# solar.net
KiCad netlist of a schematic drawn in EAGLE
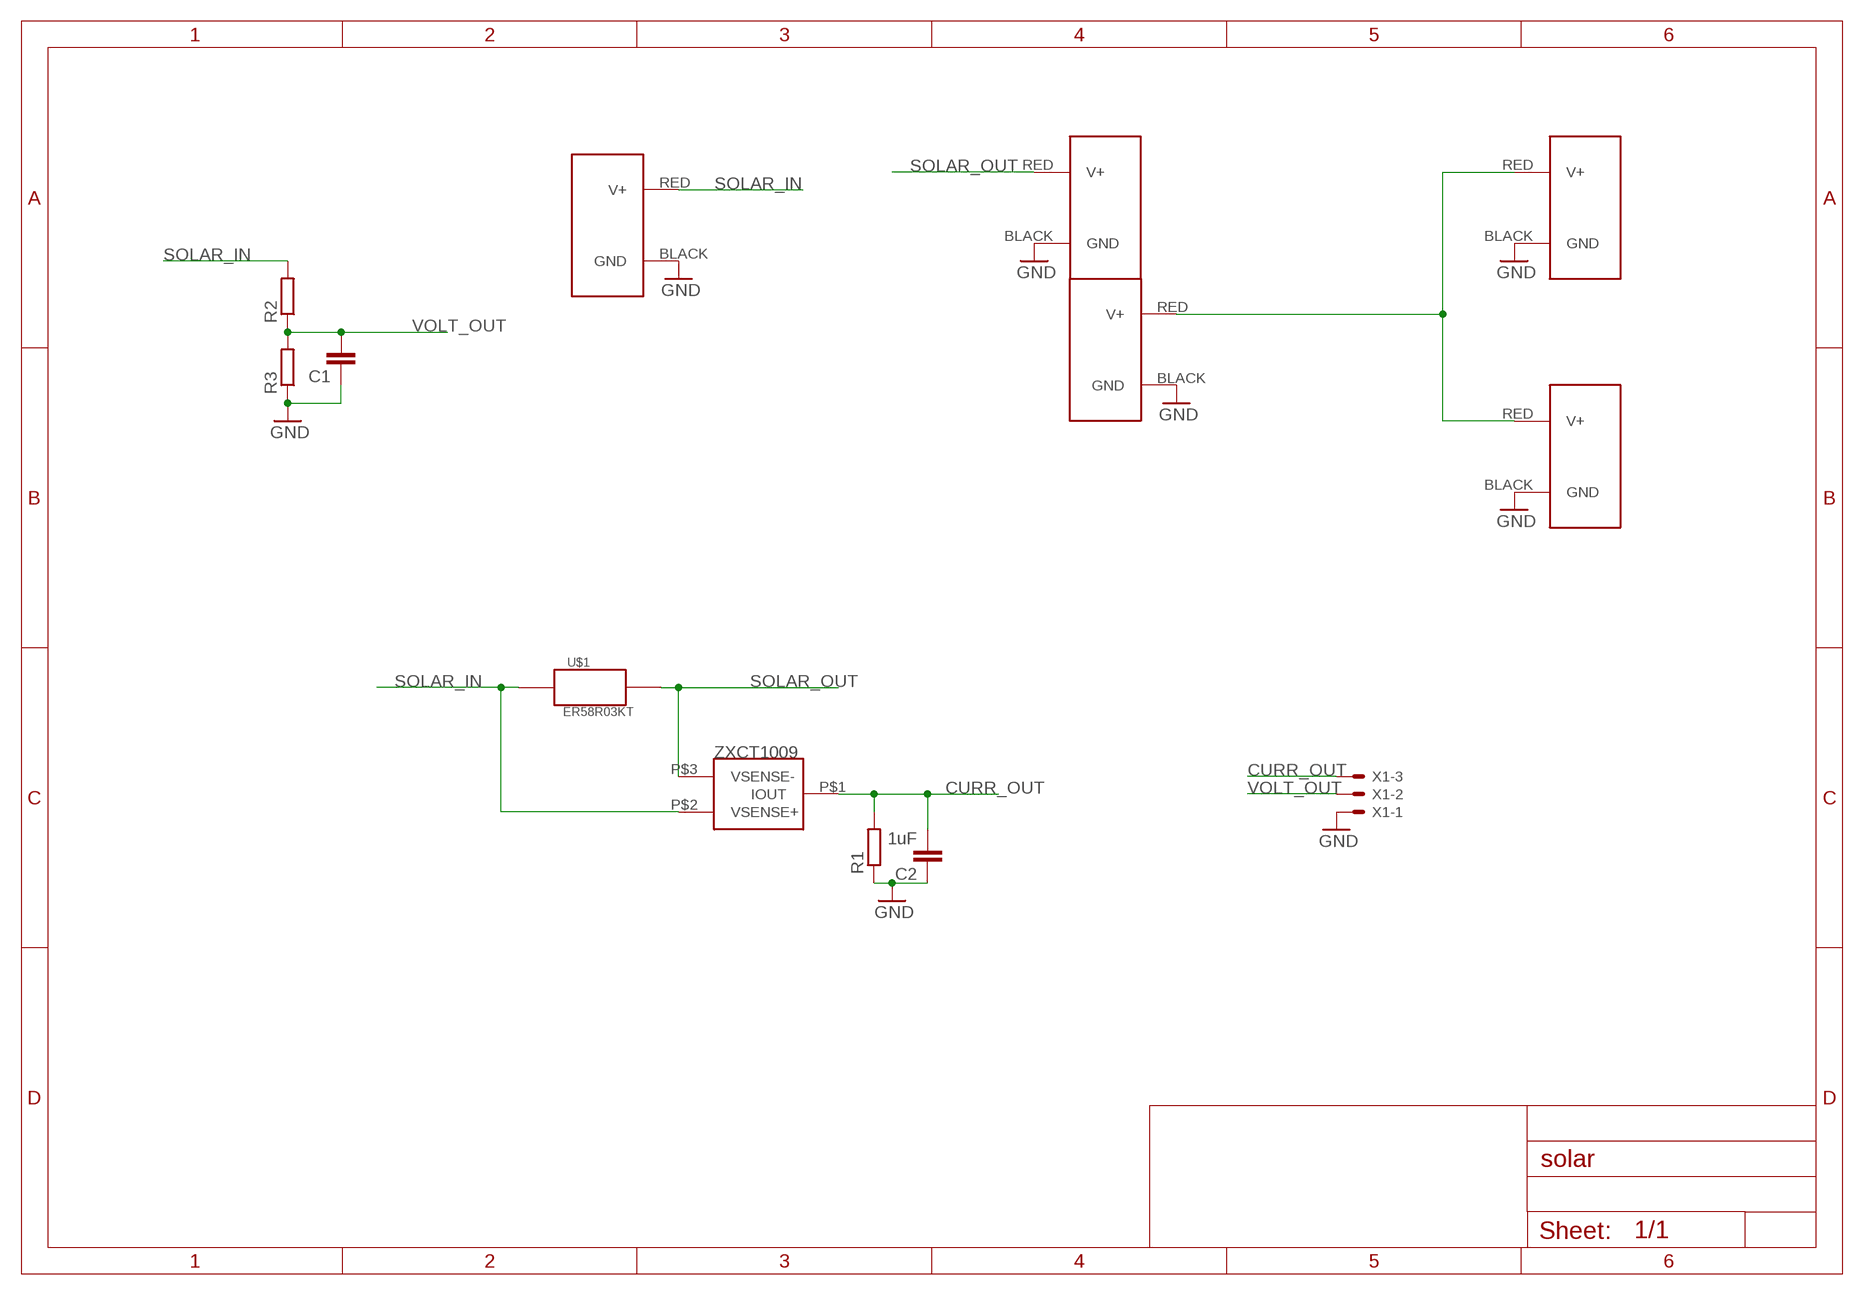
[diagram p0: schematic, sheet 1]

(export (version "E")
  (design (tool "Eeschema 10.0.6"))
  (components
    (comp (ref "C1")
      (value "C-EUC0805")
      (footprint "eagle-import:C0805")
      (libsource (lib "eagle-import") (part "C-EUC0805"))
    )
    (comp (ref "C2")
      (value "1uF")
      (footprint "eagle-import:C0805")
      (libsource (lib "eagle-import") (part "C-EUC0805"))
    )
    (comp (ref "J1")
      (value "POWERPOLE_POWER25A")
      (footprint "eagle-import:POWERPOLE_PAIR_25A")
      (libsource (lib "eagle-import") (part "POWERPOLE_POWER25A"))
    )
    (comp (ref "J2")
      (value "POWERPOLE_POWER25A")
      (footprint "eagle-import:POWERPOLE_PAIR_25A")
      (libsource (lib "eagle-import") (part "POWERPOLE_POWER25A"))
    )
    (comp (ref "J3")
      (value "POWERPOLE_POWER25A")
      (footprint "eagle-import:POWERPOLE_PAIR_25A")
      (libsource (lib "eagle-import") (part "POWERPOLE_POWER25A"))
    )
    (comp (ref "J4")
      (value "POWERPOLE_POWER25A")
      (footprint "eagle-import:POWERPOLE_PAIR_25A")
      (libsource (lib "eagle-import") (part "POWERPOLE_POWER25A"))
    )
    (comp (ref "J5")
      (value "POWERPOLE_POWER25A")
      (footprint "eagle-import:POWERPOLE_PAIR_25A")
      (libsource (lib "eagle-import") (part "POWERPOLE_POWER25A"))
    )
    (comp (ref "R1")
      (value "R-EU_R0805")
      (footprint "eagle-import:R0805")
      (libsource (lib "eagle-import") (part "R-EU_R0805"))
    )
    (comp (ref "R2")
      (value "R-EU_R0805")
      (footprint "eagle-import:R0805")
      (libsource (lib "eagle-import") (part "R-EU_R0805"))
    )
    (comp (ref "R3")
      (value "R-EU_R0805")
      (footprint "eagle-import:R0805")
      (libsource (lib "eagle-import") (part "R-EU_R0805"))
    )
    (comp (ref "U$1")
      (value "ER58R03KT")
      (footprint "eagle-import:ER58R03KT")
      (libsource (lib "eagle-import") (part "ER58R03KT"))
    )
    (comp (ref "U$2")
      (value "ZXCT1009")
      (footprint "eagle-import:ZXCT1009-SOT")
      (libsource (lib "eagle-import") (part "ZXCT1009"))
    )
    (comp (ref "X1")
      (value "KK-156-3")
      (footprint "eagle-import:KK-156-3")
      (libsource (lib "eagle-import") (part "KK-156-3"))
    )
  )
  (nets
    (net (code "1") (name "/CURR_OUT") (class "Default")
      (node (ref "C2") (pin "2") (pinfunction "2_2") (pintype "passive"))
      (node (ref "R1") (pin "2") (pinfunction "2_2") (pintype "passive"))
      (node (ref "U$2") (pin "P$1") (pinfunction "IOUT_P$1") (pintype "output"))
      (node (ref "X1") (pin "3") (pinfunction "S_3") (pintype "passive"))
    )
    (net (code "2") (name "/SOLAR_IN") (class "Default")
      (node (ref "J1") (pin "RED") (pinfunction "V+_RED") (pintype "power_in"))
      (node (ref "R2") (pin "2") (pinfunction "2_2") (pintype "passive"))
      (node (ref "U$1") (pin "P$1") (pinfunction "P$1_P$1") (pintype "passive"))
      (node (ref "U$2") (pin "P$2") (pinfunction "VSENSE+_P$2") (pintype "bidirectional"))
    )
    (net (code "3") (name "/SOLAR_OUT") (class "Default")
      (node (ref "J3") (pin "RED") (pinfunction "V+_RED") (pintype "power_in"))
      (node (ref "U$1") (pin "P$2") (pinfunction "P$2_P$2") (pintype "passive"))
      (node (ref "U$2") (pin "P$3") (pinfunction "VSENSE-_P$3") (pintype "input"))
    )
    (net (code "4") (name "/VOLT_OUT") (class "Default")
      (node (ref "C1") (pin "2") (pinfunction "2_2") (pintype "passive"))
      (node (ref "R2") (pin "1") (pinfunction "1_1") (pintype "passive"))
      (node (ref "R3") (pin "2") (pinfunction "2_2") (pintype "passive"))
      (node (ref "X1") (pin "2") (pinfunction "S_2") (pintype "passive"))
    )
    (net (code "5") (name "GND") (class "Default")
      (node (ref "C1") (pin "1") (pinfunction "1_1") (pintype "passive"))
      (node (ref "C2") (pin "1") (pinfunction "1_1") (pintype "passive"))
      (node (ref "J1") (pin "BLACK") (pinfunction "GND_BLACK") (pintype "power_in"))
      (node (ref "J2") (pin "BLACK") (pinfunction "GND_BLACK") (pintype "power_in"))
      (node (ref "J3") (pin "BLACK") (pinfunction "GND_BLACK") (pintype "power_in"))
      (node (ref "J4") (pin "BLACK") (pinfunction "GND_BLACK") (pintype "power_in"))
      (node (ref "J5") (pin "BLACK") (pinfunction "GND_BLACK") (pintype "power_in"))
      (node (ref "R1") (pin "1") (pinfunction "1_1") (pintype "passive"))
      (node (ref "R3") (pin "1") (pinfunction "1_1") (pintype "passive"))
      (node (ref "X1") (pin "1") (pinfunction "S_1") (pintype "passive"))
    )
    (net (code "6") (name "Net-(J2-V+)") (class "Default")
      (node (ref "J2") (pin "RED") (pinfunction "V+_RED") (pintype "power_in"))
      (node (ref "J4") (pin "RED") (pinfunction "V+_RED") (pintype "power_in"))
      (node (ref "J5") (pin "RED") (pinfunction "V+_RED") (pintype "power_in"))
    )
  )
)
